# matrix.net
KiCad netlist of a schematic drawn in Altium Designer
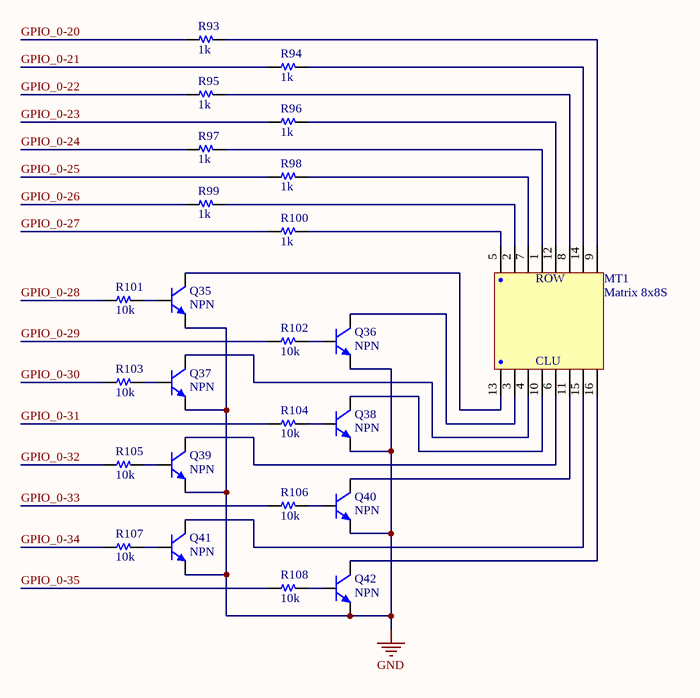
[diagram p0: matrix.SchDoc]

(export (version "E")
  (design (tool "Eeschema 10.0.6"))
  (components
    (comp (ref "MT1")
      (value "Matrix 8x8S")
      (footprint "Led Matrix 1.9mm")
      (description "Matrix 8x8,  Single colour")
      (libsource (lib "syhaunguyen") (part "LED 8x8S"))
    )
    (comp (ref "Q35")
      (value "NPN")
      (footprint "SOT-23")
      (description "NPN Bipolar Transistor")
      (libsource (lib "chipfc_libs") (part "Transistor NPN"))
    )
    (comp (ref "Q36")
      (value "NPN")
      (footprint "SOT-23")
      (description "NPN Bipolar Transistor")
      (libsource (lib "chipfc_libs") (part "Transistor NPN"))
    )
    (comp (ref "Q37")
      (value "NPN")
      (footprint "SOT-23")
      (description "NPN Bipolar Transistor")
      (libsource (lib "chipfc_libs") (part "Transistor NPN"))
    )
    (comp (ref "Q38")
      (value "NPN")
      (footprint "SOT-23")
      (description "NPN Bipolar Transistor")
      (libsource (lib "chipfc_libs") (part "Transistor NPN"))
    )
    (comp (ref "Q39")
      (value "NPN")
      (footprint "SOT-23")
      (description "NPN Bipolar Transistor")
      (libsource (lib "chipfc_libs") (part "Transistor NPN"))
    )
    (comp (ref "Q40")
      (value "NPN")
      (footprint "SOT-23")
      (description "NPN Bipolar Transistor")
      (libsource (lib "chipfc_libs") (part "Transistor NPN"))
    )
    (comp (ref "Q41")
      (value "NPN")
      (footprint "SOT-23")
      (description "NPN Bipolar Transistor")
      (libsource (lib "chipfc_libs") (part "Transistor NPN"))
    )
    (comp (ref "Q42")
      (value "NPN")
      (footprint "SOT-23")
      (description "NPN Bipolar Transistor")
      (libsource (lib "chipfc_libs") (part "Transistor NPN"))
    )
    (comp (ref "R93")
      (value "1k")
      (footprint "R 0603")
      (description "Resistor")
      (libsource (lib "chipfc_libs") (part "Resistor"))
    )
    (comp (ref "R94")
      (value "1k")
      (footprint "R 0603")
      (description "Resistor")
      (libsource (lib "chipfc_libs") (part "Resistor"))
    )
    (comp (ref "R95")
      (value "1k")
      (footprint "R 0603")
      (description "Resistor")
      (libsource (lib "chipfc_libs") (part "Resistor"))
    )
    (comp (ref "R96")
      (value "1k")
      (footprint "R 0603")
      (description "Resistor")
      (libsource (lib "chipfc_libs") (part "Resistor"))
    )
    (comp (ref "R97")
      (value "1k")
      (footprint "R 0603")
      (description "Resistor")
      (libsource (lib "chipfc_libs") (part "Resistor"))
    )
    (comp (ref "R98")
      (value "1k")
      (footprint "R 0603")
      (description "Resistor")
      (libsource (lib "chipfc_libs") (part "Resistor"))
    )
    (comp (ref "R99")
      (value "1k")
      (footprint "R 0603")
      (description "Resistor")
      (libsource (lib "chipfc_libs") (part "Resistor"))
    )
    (comp (ref "R100")
      (value "1k")
      (footprint "R 0603")
      (description "Resistor")
      (libsource (lib "chipfc_libs") (part "Resistor"))
    )
    (comp (ref "R101")
      (value "10k")
      (footprint "R 0603")
      (description "Resistor")
      (libsource (lib "chipfc_libs") (part "Resistor"))
    )
    (comp (ref "R102")
      (value "10k")
      (footprint "R 0603")
      (description "Resistor")
      (libsource (lib "chipfc_libs") (part "Resistor"))
    )
    (comp (ref "R103")
      (value "10k")
      (footprint "R 0603")
      (description "Resistor")
      (libsource (lib "chipfc_libs") (part "Resistor"))
    )
    (comp (ref "R104")
      (value "10k")
      (footprint "R 0603")
      (description "Resistor")
      (libsource (lib "chipfc_libs") (part "Resistor"))
    )
    (comp (ref "R105")
      (value "10k")
      (footprint "R 0603")
      (description "Resistor")
      (libsource (lib "chipfc_libs") (part "Resistor"))
    )
    (comp (ref "R106")
      (value "10k")
      (footprint "R 0603")
      (description "Resistor")
      (libsource (lib "chipfc_libs") (part "Resistor"))
    )
    (comp (ref "R107")
      (value "10k")
      (footprint "R 0603")
      (description "Resistor")
      (libsource (lib "chipfc_libs") (part "Resistor"))
    )
    (comp (ref "R108")
      (value "10k")
      (footprint "R 0603")
      (description "Resistor")
      (libsource (lib "chipfc_libs") (part "Resistor"))
    )
  )
  (nets
    (net (code "1") (name "/GPIO_0-20") (class "Default")
      (node (ref "R93") (pin "1") (pinfunction "1_1") (pintype "passive"))
    )
    (net (code "2") (name "/GPIO_0-21") (class "Default")
      (node (ref "R94") (pin "1") (pinfunction "1_1") (pintype "passive"))
    )
    (net (code "3") (name "/GPIO_0-22") (class "Default")
      (node (ref "R95") (pin "1") (pinfunction "1_1") (pintype "passive"))
    )
    (net (code "4") (name "/GPIO_0-23") (class "Default")
      (node (ref "R96") (pin "1") (pinfunction "1_1") (pintype "passive"))
    )
    (net (code "5") (name "/GPIO_0-24") (class "Default")
      (node (ref "R97") (pin "1") (pinfunction "1_1") (pintype "passive"))
    )
    (net (code "6") (name "/GPIO_0-25") (class "Default")
      (node (ref "R98") (pin "1") (pinfunction "1_1") (pintype "passive"))
    )
    (net (code "7") (name "/GPIO_0-26") (class "Default")
      (node (ref "R99") (pin "1") (pinfunction "1_1") (pintype "passive"))
    )
    (net (code "8") (name "/GPIO_0-27") (class "Default")
      (node (ref "R100") (pin "1") (pinfunction "1_1") (pintype "passive"))
    )
    (net (code "9") (name "/GPIO_0-28") (class "Default")
      (node (ref "R101") (pin "1") (pinfunction "1_1") (pintype "passive"))
    )
    (net (code "10") (name "/GPIO_0-29") (class "Default")
      (node (ref "R102") (pin "1") (pinfunction "1_1") (pintype "passive"))
    )
    (net (code "11") (name "/GPIO_0-30") (class "Default")
      (node (ref "R103") (pin "1") (pinfunction "1_1") (pintype "passive"))
    )
    (net (code "12") (name "/GPIO_0-31") (class "Default")
      (node (ref "R104") (pin "1") (pinfunction "1_1") (pintype "passive"))
    )
    (net (code "13") (name "/GPIO_0-32") (class "Default")
      (node (ref "R105") (pin "1") (pinfunction "1_1") (pintype "passive"))
    )
    (net (code "14") (name "/GPIO_0-33") (class "Default")
      (node (ref "R106") (pin "1") (pinfunction "1_1") (pintype "passive"))
    )
    (net (code "15") (name "/GPIO_0-34") (class "Default")
      (node (ref "R107") (pin "1") (pinfunction "1_1") (pintype "passive"))
    )
    (net (code "16") (name "/GPIO_0-35") (class "Default")
      (node (ref "R108") (pin "1") (pinfunction "1_1") (pintype "passive"))
    )
    (net (code "17") (name "GND") (class "Default")
      (node (ref "Q35") (pin "2") (pinfunction "E_2") (pintype "passive"))
      (node (ref "Q36") (pin "2") (pinfunction "E_2") (pintype "passive"))
      (node (ref "Q37") (pin "2") (pinfunction "E_2") (pintype "passive"))
      (node (ref "Q38") (pin "2") (pinfunction "E_2") (pintype "passive"))
      (node (ref "Q39") (pin "2") (pinfunction "E_2") (pintype "passive"))
      (node (ref "Q40") (pin "2") (pinfunction "E_2") (pintype "passive"))
      (node (ref "Q41") (pin "2") (pinfunction "E_2") (pintype "passive"))
      (node (ref "Q42") (pin "2") (pinfunction "E_2") (pintype "passive"))
    )
    (net (code "18") (name "Net-(MT1-C1)") (class "Default")
      (node (ref "MT1") (pin "13") (pinfunction "C1_13") (pintype "passive"))
      (node (ref "Q35") (pin "3") (pinfunction "C_3") (pintype "passive"))
    )
    (net (code "19") (name "Net-(MT1-C2)") (class "Default")
      (node (ref "MT1") (pin "3") (pinfunction "C2_3") (pintype "passive"))
      (node (ref "Q36") (pin "3") (pinfunction "C_3") (pintype "passive"))
    )
    (net (code "20") (name "Net-(MT1-C3)") (class "Default")
      (node (ref "MT1") (pin "4") (pinfunction "C3_4") (pintype "passive"))
      (node (ref "Q37") (pin "3") (pinfunction "C_3") (pintype "passive"))
    )
    (net (code "21") (name "Net-(MT1-C4)") (class "Default")
      (node (ref "MT1") (pin "10") (pinfunction "C4_10") (pintype "passive"))
      (node (ref "Q38") (pin "3") (pinfunction "C_3") (pintype "passive"))
    )
    (net (code "22") (name "Net-(MT1-C5)") (class "Default")
      (node (ref "MT1") (pin "6") (pinfunction "C5_6") (pintype "passive"))
      (node (ref "Q39") (pin "3") (pinfunction "C_3") (pintype "passive"))
    )
    (net (code "23") (name "Net-(MT1-C6)") (class "Default")
      (node (ref "MT1") (pin "11") (pinfunction "C6_11") (pintype "passive"))
      (node (ref "Q40") (pin "3") (pinfunction "C_3") (pintype "passive"))
    )
    (net (code "24") (name "Net-(MT1-C7)") (class "Default")
      (node (ref "MT1") (pin "15") (pinfunction "C7_15") (pintype "passive"))
      (node (ref "Q41") (pin "3") (pinfunction "C_3") (pintype "passive"))
    )
    (net (code "25") (name "Net-(MT1-C8)") (class "Default")
      (node (ref "MT1") (pin "16") (pinfunction "C8_16") (pintype "passive"))
      (node (ref "Q42") (pin "3") (pinfunction "C_3") (pintype "passive"))
    )
    (net (code "26") (name "Net-(MT1-H1)") (class "Default")
      (node (ref "MT1") (pin "5") (pinfunction "H1_5") (pintype "passive"))
      (node (ref "R100") (pin "2") (pinfunction "2_2") (pintype "passive"))
    )
    (net (code "27") (name "Net-(MT1-H2)") (class "Default")
      (node (ref "MT1") (pin "2") (pinfunction "H2_2") (pintype "passive"))
      (node (ref "R99") (pin "2") (pinfunction "2_2") (pintype "passive"))
    )
    (net (code "28") (name "Net-(MT1-H3)") (class "Default")
      (node (ref "MT1") (pin "7") (pinfunction "H3_7") (pintype "passive"))
      (node (ref "R98") (pin "2") (pinfunction "2_2") (pintype "passive"))
    )
    (net (code "29") (name "Net-(MT1-H4)") (class "Default")
      (node (ref "MT1") (pin "1") (pinfunction "H4_1") (pintype "passive"))
      (node (ref "R97") (pin "2") (pinfunction "2_2") (pintype "passive"))
    )
    (net (code "30") (name "Net-(MT1-H5)") (class "Default")
      (node (ref "MT1") (pin "12") (pinfunction "H5_12") (pintype "passive"))
      (node (ref "R96") (pin "2") (pinfunction "2_2") (pintype "passive"))
    )
    (net (code "31") (name "Net-(MT1-H6)") (class "Default")
      (node (ref "MT1") (pin "8") (pinfunction "H6_8") (pintype "passive"))
      (node (ref "R95") (pin "2") (pinfunction "2_2") (pintype "passive"))
    )
    (net (code "32") (name "Net-(MT1-H7)") (class "Default")
      (node (ref "MT1") (pin "14") (pinfunction "H7_14") (pintype "passive"))
      (node (ref "R94") (pin "2") (pinfunction "2_2") (pintype "passive"))
    )
    (net (code "33") (name "Net-(MT1-H8)") (class "Default")
      (node (ref "MT1") (pin "9") (pinfunction "H8_9") (pintype "passive"))
      (node (ref "R93") (pin "2") (pinfunction "2_2") (pintype "passive"))
    )
    (net (code "34") (name "Net-(Q35-B)") (class "Default")
      (node (ref "Q35") (pin "1") (pinfunction "B_1") (pintype "passive"))
      (node (ref "R101") (pin "2") (pinfunction "2_2") (pintype "passive"))
    )
    (net (code "35") (name "Net-(Q36-B)") (class "Default")
      (node (ref "Q36") (pin "1") (pinfunction "B_1") (pintype "passive"))
      (node (ref "R102") (pin "2") (pinfunction "2_2") (pintype "passive"))
    )
    (net (code "36") (name "Net-(Q37-B)") (class "Default")
      (node (ref "Q37") (pin "1") (pinfunction "B_1") (pintype "passive"))
      (node (ref "R103") (pin "2") (pinfunction "2_2") (pintype "passive"))
    )
    (net (code "37") (name "Net-(Q38-B)") (class "Default")
      (node (ref "Q38") (pin "1") (pinfunction "B_1") (pintype "passive"))
      (node (ref "R104") (pin "2") (pinfunction "2_2") (pintype "passive"))
    )
    (net (code "38") (name "Net-(Q39-B)") (class "Default")
      (node (ref "Q39") (pin "1") (pinfunction "B_1") (pintype "passive"))
      (node (ref "R105") (pin "2") (pinfunction "2_2") (pintype "passive"))
    )
    (net (code "39") (name "Net-(Q40-B)") (class "Default")
      (node (ref "Q40") (pin "1") (pinfunction "B_1") (pintype "passive"))
      (node (ref "R106") (pin "2") (pinfunction "2_2") (pintype "passive"))
    )
    (net (code "40") (name "Net-(Q41-B)") (class "Default")
      (node (ref "Q41") (pin "1") (pinfunction "B_1") (pintype "passive"))
      (node (ref "R107") (pin "2") (pinfunction "2_2") (pintype "passive"))
    )
    (net (code "41") (name "Net-(Q42-B)") (class "Default")
      (node (ref "Q42") (pin "1") (pinfunction "B_1") (pintype "passive"))
      (node (ref "R108") (pin "2") (pinfunction "2_2") (pintype "passive"))
    )
  )
)
